# STorM32_NT_Display_v12.net
KiCad netlist of a schematic drawn in EAGLE
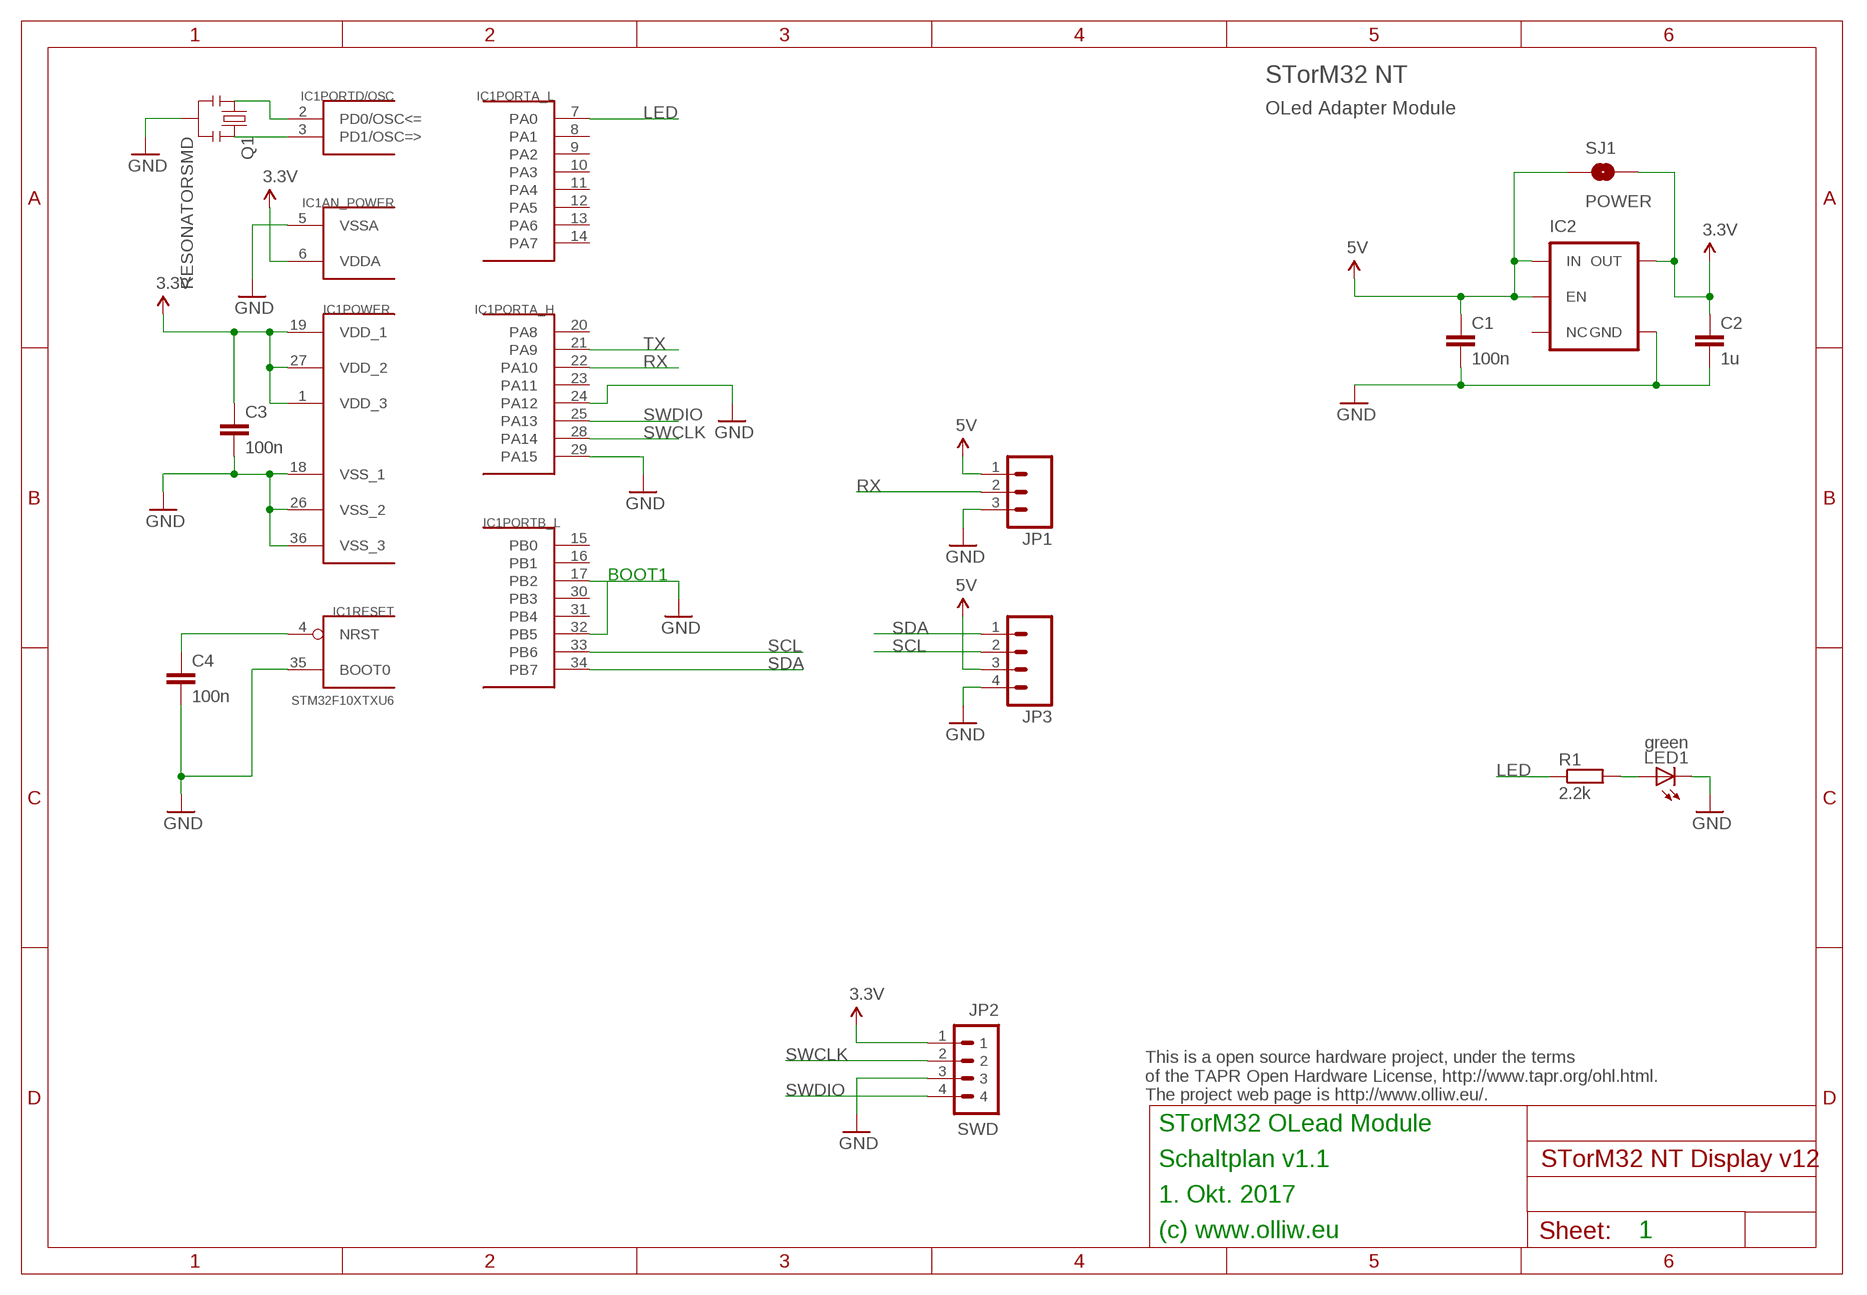
[diagram p0: schematic, sheet 1]

(export (version "E")
  (design (tool "Eeschema 10.0.6"))
  (components
    (comp (ref "C1")
      (value "100n")
      (footprint "eagle-import:C0603")
      (libsource (lib "eagle-import") (part "C-EUC0603"))
    )
    (comp (ref "C2")
      (value "1u")
      (footprint "eagle-import:C0603")
      (libsource (lib "eagle-import") (part "C-EUC0603"))
    )
    (comp (ref "C3")
      (value "100n")
      (footprint "eagle-import:C0603")
      (libsource (lib "eagle-import") (part "C-EUC0603"))
    )
    (comp (ref "C4")
      (value "100n")
      (footprint "eagle-import:C0603")
      (libsource (lib "eagle-import") (part "C-EUC0603"))
    )
    (comp (ref "IC1")
      (value "STM32F10XTXU6")
      (footprint "eagle-import:VFQFPN36")
      (libsource (lib "eagle-import") (part "STM32F10XTXU6"))
    )
    (comp (ref "IC2")
      (value "V_REG_TPS76433SOT23-5")
      (footprint "eagle-import:SOT23-5")
      (libsource (lib "eagle-import") (part "V_REG_TPS76433SOT23-5"))
    )
    (comp (ref "JP1")
      (value "M03PTH")
      (footprint "eagle-import:1X03")
      (libsource (lib "eagle-import") (part "M03PTH"))
    )
    (comp (ref "JP2")
      (value "SWD")
      (footprint "eagle-import:4X1_1P27_OCT_BILEX")
      (libsource (lib "eagle-import") (part "P4X1_1P27-OCT_BILEX"))
    )
    (comp (ref "JP3")
      (value "M04PTH")
      (footprint "eagle-import:1X04")
      (libsource (lib "eagle-import") (part "M04PTH"))
    )
    (comp (ref "LED1")
      (value "green")
      (footprint "eagle-import:CHIPLED_0603")
      (libsource (lib "eagle-import") (part "LEDCHIPLED_0603"))
    )
    (comp (ref "Q1")
      (value "RESONATORSMD")
      (footprint "eagle-import:RESONATOR-SMD")
      (libsource (lib "eagle-import") (part "RESONATORSMD"))
    )
    (comp (ref "R1")
      (value "2.2k")
      (footprint "eagle-import:R0603")
      (libsource (lib "eagle-import") (part "R-EU_R0603"))
    )
    (comp (ref "SJ1")
      (value "POWER")
      (footprint "eagle-import:SJ_2S-NO")
      (libsource (lib "eagle-import") (part "SOLDERJUMPERNO"))
    )
  )
  (nets
    (net (code "1") (name "/LED") (class "Default")
      (node (ref "IC1") (pin "7") (pinfunction "PA0_7") (pintype "bidirectional"))
      (node (ref "R1") (pin "1") (pinfunction "1_1") (pintype "passive"))
    )
    (net (code "2") (name "/RX") (class "Default")
      (node (ref "IC1") (pin "22") (pinfunction "PA10_22") (pintype "bidirectional"))
      (node (ref "JP1") (pin "2") (pinfunction "2_2") (pintype "passive"))
    )
    (net (code "3") (name "/SCL") (class "Default")
      (node (ref "IC1") (pin "33") (pinfunction "PB6_33") (pintype "bidirectional"))
      (node (ref "JP3") (pin "2") (pinfunction "2_2") (pintype "passive"))
    )
    (net (code "4") (name "/SDA") (class "Default")
      (node (ref "IC1") (pin "34") (pinfunction "PB7_34") (pintype "bidirectional"))
      (node (ref "JP3") (pin "1") (pinfunction "1_1") (pintype "passive"))
    )
    (net (code "5") (name "/SWCLK") (class "Default")
      (node (ref "IC1") (pin "28") (pinfunction "PA14_28") (pintype "bidirectional"))
      (node (ref "JP2") (pin "2") (pinfunction "2_2") (pintype "passive"))
    )
    (net (code "6") (name "/SWDIO") (class "Default")
      (node (ref "IC1") (pin "25") (pinfunction "PA13_25") (pintype "bidirectional"))
      (node (ref "JP2") (pin "4") (pinfunction "4_4") (pintype "passive"))
    )
    (net (code "7") (name "/TX") (class "Default")
      (node (ref "IC1") (pin "21") (pinfunction "PA9_21") (pintype "bidirectional"))
    )
    (net (code "8") (name "3.3V") (class "Default")
      (node (ref "C2") (pin "1") (pinfunction "1_1") (pintype "passive"))
      (node (ref "C3") (pin "1") (pinfunction "1_1") (pintype "passive"))
      (node (ref "IC1") (pin "1") (pinfunction "VDD_3_1") (pintype "power_in"))
      (node (ref "IC1") (pin "19") (pinfunction "VDD_1_19") (pintype "power_in"))
      (node (ref "IC1") (pin "27") (pinfunction "VDD_2_27") (pintype "power_in"))
      (node (ref "IC1") (pin "6") (pinfunction "VDDA_6") (pintype "power_in"))
      (node (ref "IC2") (pin "5") (pinfunction "OUT_5") (pintype "passive"))
      (node (ref "JP2") (pin "1") (pinfunction "1_1") (pintype "passive"))
      (node (ref "SJ1") (pin "2") (pinfunction "2_2") (pintype "passive"))
    )
    (net (code "9") (name "5V") (class "Default")
      (node (ref "C1") (pin "1") (pinfunction "1_1") (pintype "passive"))
      (node (ref "IC2") (pin "1") (pinfunction "IN_1") (pintype "input"))
      (node (ref "IC2") (pin "3") (pinfunction "EN_3") (pintype "input"))
      (node (ref "JP1") (pin "1") (pinfunction "1_1") (pintype "passive"))
      (node (ref "JP3") (pin "3") (pinfunction "3_3") (pintype "passive"))
      (node (ref "SJ1") (pin "1") (pinfunction "1_1") (pintype "passive"))
    )
    (net (code "10") (name "GND") (class "Default")
      (node (ref "C1") (pin "2") (pinfunction "2_2") (pintype "passive"))
      (node (ref "C2") (pin "2") (pinfunction "2_2") (pintype "passive"))
      (node (ref "C3") (pin "2") (pinfunction "2_2") (pintype "passive"))
      (node (ref "C4") (pin "2") (pinfunction "2_2") (pintype "passive"))
      (node (ref "IC1") (pin "17") (pinfunction "PB2_17") (pintype "bidirectional"))
      (node (ref "IC1") (pin "18") (pinfunction "VSS_1_18") (pintype "power_in"))
      (node (ref "IC1") (pin "24") (pinfunction "PA12_24") (pintype "bidirectional"))
      (node (ref "IC1") (pin "26") (pinfunction "VSS_2_26") (pintype "power_in"))
      (node (ref "IC1") (pin "29") (pinfunction "PA15_29") (pintype "bidirectional"))
      (node (ref "IC1") (pin "32") (pinfunction "PB5_32") (pintype "bidirectional"))
      (node (ref "IC1") (pin "35") (pinfunction "BOOT0_35") (pintype "input"))
      (node (ref "IC1") (pin "36") (pinfunction "VSS_3_36") (pintype "power_in"))
      (node (ref "IC1") (pin "5") (pinfunction "VSSA_5") (pintype "power_in"))
      (node (ref "IC2") (pin "2") (pinfunction "GND_2") (pintype "input"))
      (node (ref "JP1") (pin "3") (pinfunction "3_3") (pintype "passive"))
      (node (ref "JP2") (pin "3") (pinfunction "3_3") (pintype "passive"))
      (node (ref "JP3") (pin "4") (pinfunction "4_4") (pintype "passive"))
      (node (ref "LED1") (pin "C") (pinfunction "C_C") (pintype "passive"))
      (node (ref "Q1") (pin "2") (pinfunction "2_2") (pintype "passive"))
    )
    (net (code "11") (name "Net-(IC1E-PD0{slash}OSC<=)") (class "Default")
      (node (ref "IC1") (pin "2") (pinfunction "PD0/OSC<=_2") (pintype "bidirectional"))
      (node (ref "Q1") (pin "1") (pinfunction "1_1") (pintype "passive"))
    )
    (net (code "12") (name "Net-(IC1E-PD1{slash}OSC=>)") (class "Default")
      (node (ref "IC1") (pin "3") (pinfunction "PD1/OSC=>_3") (pintype "bidirectional"))
      (node (ref "Q1") (pin "3") (pinfunction "3_3") (pintype "passive"))
    )
    (net (code "13") (name "Net-(IC1G-NRST)") (class "Default")
      (node (ref "C4") (pin "1") (pinfunction "1_1") (pintype "passive"))
      (node (ref "IC1") (pin "4") (pinfunction "NRST_4") (pintype "input"))
    )
    (net (code "14") (name "Net-(LED1-PadA)") (class "Default")
      (node (ref "LED1") (pin "A") (pinfunction "A_A") (pintype "passive"))
      (node (ref "R1") (pin "2") (pinfunction "2_2") (pintype "passive"))
    )
    (net (code "15") (name "unconnected-(IC1B-PA8-Pad20)") (class "Default")
      (node (ref "IC1") (pin "20") (pinfunction "PA8_20") (pintype "bidirectional"))
    )
    (net (code "16") (name "unconnected-(IC1B-PA11-Pad23)") (class "Default")
      (node (ref "IC1") (pin "23") (pinfunction "PA11_23") (pintype "bidirectional"))
    )
    (net (code "17") (name "unconnected-(IC1C-PA1-Pad8)") (class "Default")
      (node (ref "IC1") (pin "8") (pinfunction "PA1_8") (pintype "bidirectional"))
    )
    (net (code "18") (name "unconnected-(IC1C-PA2-Pad9)") (class "Default")
      (node (ref "IC1") (pin "9") (pinfunction "PA2_9") (pintype "bidirectional"))
    )
    (net (code "19") (name "unconnected-(IC1C-PA3-Pad10)") (class "Default")
      (node (ref "IC1") (pin "10") (pinfunction "PA3_10") (pintype "bidirectional"))
    )
    (net (code "20") (name "unconnected-(IC1C-PA4-Pad11)") (class "Default")
      (node (ref "IC1") (pin "11") (pinfunction "PA4_11") (pintype "bidirectional"))
    )
    (net (code "21") (name "unconnected-(IC1C-PA5-Pad12)") (class "Default")
      (node (ref "IC1") (pin "12") (pinfunction "PA5_12") (pintype "bidirectional"))
    )
    (net (code "22") (name "unconnected-(IC1C-PA6-Pad13)") (class "Default")
      (node (ref "IC1") (pin "13") (pinfunction "PA6_13") (pintype "bidirectional"))
    )
    (net (code "23") (name "unconnected-(IC1C-PA7-Pad14)") (class "Default")
      (node (ref "IC1") (pin "14") (pinfunction "PA7_14") (pintype "bidirectional"))
    )
    (net (code "24") (name "unconnected-(IC1D-PB0-Pad15)") (class "Default")
      (node (ref "IC1") (pin "15") (pinfunction "PB0_15") (pintype "bidirectional"))
    )
    (net (code "25") (name "unconnected-(IC1D-PB1-Pad16)") (class "Default")
      (node (ref "IC1") (pin "16") (pinfunction "PB1_16") (pintype "bidirectional"))
    )
    (net (code "26") (name "unconnected-(IC1D-PB3-Pad30)") (class "Default")
      (node (ref "IC1") (pin "30") (pinfunction "PB3_30") (pintype "bidirectional"))
    )
    (net (code "27") (name "unconnected-(IC1D-PB4-Pad31)") (class "Default")
      (node (ref "IC1") (pin "31") (pinfunction "PB4_31") (pintype "bidirectional"))
    )
    (net (code "28") (name "unconnected-(IC2-NC-Pad4)") (class "Default")
      (node (ref "IC2") (pin "4") (pinfunction "NC_4") (pintype "input"))
    )
  )
)
